# nguyenly.net
KiCad netlist of a schematic drawn in Altium Designer
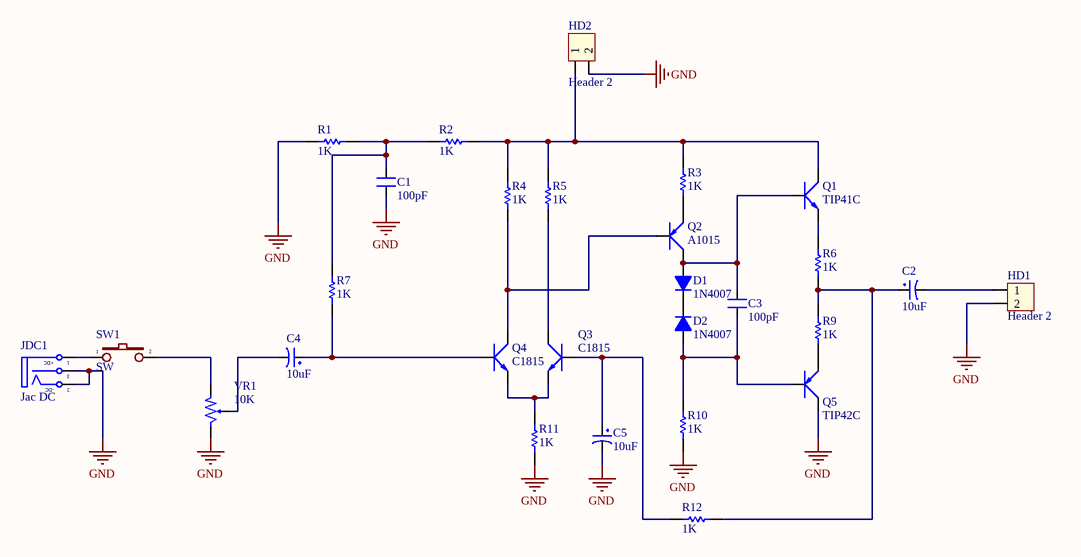
[diagram p0: nguyenly.SchDoc]

(export (version "E")
  (design (tool "Eeschema 10.0.6"))
  (components
    (comp (ref "C1")
      (value "100pF")
      (footprint "CN1")
      (description "Cap np  1pF - 472pF")
      (libsource (lib "Thuvien3D") (part "CN1"))
    )
    (comp (ref "C2")
      (value "10uF")
      (footprint "CP1/2")
      (description "Cap P  0,1uF < 22uF , 16 - 50V")
      (libsource (lib "") (part "CP1_1"))
    )
    (comp (ref "C3")
      (value "100pF")
      (footprint "CN1")
      (description "Cap np  1pF - 472pF")
      (libsource (lib "Thuvien3D") (part "CN1"))
    )
    (comp (ref "C4")
      (value "10uF")
      (footprint "CP1/2")
      (description "Cap P  0,1uF < 22uF , 16 - 50V")
      (libsource (lib "") (part "CP1_1"))
    )
    (comp (ref "C5")
      (value "10uF")
      (footprint "CP1/2")
      (description "Cap P  0,1uF < 22uF , 16 - 50V")
      (libsource (lib "Thuvien3D") (part "CP1"))
    )
    (comp (ref "D1")
      (value "1N4007")
      (footprint "D1A")
      (description "Diode 1A")
      (libsource (lib "Thuvien3D") (part "D1A"))
    )
    (comp (ref "D2")
      (value "1N4007")
      (footprint "D1A")
      (description "Diode 1A")
      (libsource (lib "Thuvien3D") (part "D1A"))
    )
    (comp (ref "HD1")
      (value "Header 2")
      (footprint "HED2")
      (description "Header 2 (Green)")
      (libsource (lib "Thuvien3D") (part "Hed2"))
    )
    (comp (ref "HD2")
      (value "Header 2")
      (footprint "HED2")
      (description "Header 2 (Green)")
      (libsource (lib "") (part "Hed2_1"))
    )
    (comp (ref "JDC1")
      (value "Jac DC")
      (footprint "DC-IN")
      (description "Jac DC input")
      (libsource (lib "Thuvien3D") (part "DCIN"))
    )
    (comp (ref "Q1")
      (value "TIP41C")
      (footprint "QTO-220")
      (description "NPN 2W, BCE")
      (libsource (lib "Thuvien3D") (part "TIP41C"))
    )
    (comp (ref "Q2")
      (value "A1015")
      (footprint "QTO-92")
      (description "PNP 600mW, ECB")
      (libsource (lib "Thuvien3D") (part "A1015"))
    )
    (comp (ref "Q3")
      (value "C1815")
      (footprint "QTO-92")
      (description "NPN 600mW, ECB")
      (libsource (lib "Thuvien3D") (part "C1815"))
    )
    (comp (ref "Q4")
      (value "C1815")
      (footprint "QTO-92")
      (description "NPN 600mW, ECB")
      (libsource (lib "Thuvien3D") (part "C1815"))
    )
    (comp (ref "Q5")
      (value "TIP42C")
      (footprint "QTO-220")
      (description "PNP 2W, BCE")
      (libsource (lib "Thuvien3D") (part "TIP42C"))
    )
    (comp (ref "R1")
      (value "1K")
      (footprint "R1/4W")
      (description "Resistor")
      (fields
        (field (name "MANUFACTURER") "Generic Components")
        (field (name "Comment") "Res1")
        (field (name "PUBLISHER") "Altium Hobart Technology Centre")
      )
      (libsource (lib "Thuvien3D") (part "Res1_1"))
    )
    (comp (ref "R2")
      (value "1K")
      (footprint "R1/4W")
      (description "Resistor")
      (fields
        (field (name "MANUFACTURER") "Generic Components")
        (field (name "Comment") "Res1")
        (field (name "PUBLISHER") "Altium Hobart Technology Centre")
      )
      (libsource (lib "Thuvien3D") (part "Res1_1"))
    )
    (comp (ref "R3")
      (value "1K")
      (footprint "R1/4W")
      (description "Resistor")
      (fields
        (field (name "MANUFACTURER") "Generic Components")
        (field (name "Comment") "Res1")
        (field (name "PUBLISHER") "Altium Hobart Technology Centre")
      )
      (libsource (lib "Thuvien3D") (part "Res1_1"))
    )
    (comp (ref "R4")
      (value "1K")
      (footprint "R1/4W")
      (description "Resistor")
      (fields
        (field (name "MANUFACTURER") "Generic Components")
        (field (name "Comment") "Res1")
        (field (name "PUBLISHER") "Altium Hobart Technology Centre")
      )
      (libsource (lib "Thuvien3D") (part "Res1_1"))
    )
    (comp (ref "R5")
      (value "1K")
      (footprint "R1/4W")
      (description "Resistor")
      (fields
        (field (name "MANUFACTURER") "Generic Components")
        (field (name "Comment") "Res1")
        (field (name "PUBLISHER") "Altium Hobart Technology Centre")
      )
      (libsource (lib "Thuvien3D") (part "Res1_1"))
    )
    (comp (ref "R6")
      (value "1K")
      (footprint "R1/4W")
      (description "Resistor")
      (fields
        (field (name "MANUFACTURER") "Generic Components")
        (field (name "Comment") "Res1")
        (field (name "PUBLISHER") "Altium Hobart Technology Centre")
      )
      (libsource (lib "Thuvien3D") (part "Res1_1"))
    )
    (comp (ref "R7")
      (value "1K")
      (footprint "R1/4W")
      (description "Resistor")
      (fields
        (field (name "MANUFACTURER") "Generic Components")
        (field (name "Comment") "Res1")
        (field (name "PUBLISHER") "Altium Hobart Technology Centre")
      )
      (libsource (lib "Thuvien3D") (part "Res1_1"))
    )
    (comp (ref "R9")
      (value "1K")
      (footprint "R1/4W")
      (description "Resistor")
      (fields
        (field (name "MANUFACTURER") "Generic Components")
        (field (name "Comment") "Res1")
        (field (name "PUBLISHER") "Altium Hobart Technology Centre")
      )
      (libsource (lib "Thuvien3D") (part "Res1_1"))
    )
    (comp (ref "R10")
      (value "1K")
      (footprint "R1/4W")
      (description "Resistor")
      (fields
        (field (name "MANUFACTURER") "Generic Components")
        (field (name "Comment") "Res1")
        (field (name "PUBLISHER") "Altium Hobart Technology Centre")
      )
      (libsource (lib "Thuvien3D") (part "Res1_1"))
    )
    (comp (ref "R11")
      (value "1K")
      (footprint "R1/4W")
      (description "Resistor")
      (fields
        (field (name "MANUFACTURER") "Generic Components")
        (field (name "Comment") "Res1")
        (field (name "PUBLISHER") "Altium Hobart Technology Centre")
      )
      (libsource (lib "Thuvien3D") (part "Res1_1"))
    )
    (comp (ref "R12")
      (value "1K")
      (footprint "R1/4W")
      (description "Resistor")
      (fields
        (field (name "MANUFACTURER") "Generic Components")
        (field (name "Comment") "Res1")
        (field (name "PUBLISHER") "Altium Hobart Technology Centre")
      )
      (libsource (lib "Thuvien3D") (part "Res1_1"))
    )
    (comp (ref "SW1")
      (value "SW")
      (footprint "SW2")
      (description "Switch button 2 pin")
      (libsource (lib "Thuvien3D") (part "SW2"))
    )
    (comp (ref "VR1")
      (value "10K")
      (footprint "VR")
      (description "Var Resistor")
      (libsource (lib "Thuvien3D") (part "VR1"))
    )
  )
  (nets
    (net (code "1") (name "GND") (class "Default")
      (node (ref "C1") (pin "1") (pinfunction "1_1") (pintype "passive"))
      (node (ref "C5") (pin "2") (pinfunction "2_2") (pintype "passive"))
      (node (ref "HD1") (pin "2") (pinfunction "2_2") (pintype "passive"))
      (node (ref "HD2") (pin "2") (pinfunction "2_2") (pintype "passive"))
      (node (ref "JDC1") (pin "2") (pinfunction "TN_2") (pintype "passive"))
      (node (ref "JDC1") (pin "3") (pinfunction "S_3") (pintype "power_in"))
      (node (ref "Q5") (pin "2") (pinfunction "C_2") (pintype "passive"))
      (node (ref "R1") (pin "2") (pinfunction "2_2") (pintype "passive"))
      (node (ref "R10") (pin "2") (pinfunction "2_2") (pintype "passive"))
      (node (ref "R11") (pin "2") (pinfunction "2_2") (pintype "passive"))
      (node (ref "VR1") (pin "3") (pinfunction "3_3") (pintype "passive"))
    )
    (net (code "2") (name "Net-(C1-Pad2)") (class "Default")
      (node (ref "C1") (pin "2") (pinfunction "2_2") (pintype "passive"))
      (node (ref "R1") (pin "1") (pinfunction "1_1") (pintype "passive"))
      (node (ref "R2") (pin "2") (pinfunction "2_2") (pintype "passive"))
      (node (ref "R7") (pin "1") (pinfunction "1_1") (pintype "passive"))
    )
    (net (code "3") (name "Net-(C2-Pad1)") (class "Default")
      (node (ref "C2") (pin "1") (pinfunction "1_1") (pintype "passive"))
      (node (ref "R12") (pin "2") (pinfunction "2_2") (pintype "passive"))
      (node (ref "R6") (pin "2") (pinfunction "2_2") (pintype "passive"))
      (node (ref "R9") (pin "1") (pinfunction "1_1") (pintype "passive"))
    )
    (net (code "4") (name "Net-(C2-Pad2)") (class "Default")
      (node (ref "C2") (pin "2") (pinfunction "2_2") (pintype "passive"))
      (node (ref "HD1") (pin "1") (pinfunction "1_1") (pintype "passive"))
    )
    (net (code "5") (name "Net-(C4-Pad2)") (class "Default")
      (node (ref "C4") (pin "2") (pinfunction "2_2") (pintype "passive"))
      (node (ref "VR1") (pin "2") (pinfunction "2_2") (pintype "passive"))
    )
    (net (code "6") (name "Net-(D1-A)") (class "Default")
      (node (ref "C3") (pin "2") (pinfunction "2_2") (pintype "passive"))
      (node (ref "D1") (pin "1") (pinfunction "A_1") (pintype "passive"))
      (node (ref "Q1") (pin "1") (pinfunction "B_1") (pintype "passive"))
      (node (ref "Q2") (pin "2") (pinfunction "C_2") (pintype "passive"))
    )
    (net (code "7") (name "Net-(D1-K)") (class "Default")
      (node (ref "D1") (pin "2") (pinfunction "K_2") (pintype "passive"))
      (node (ref "D2") (pin "2") (pinfunction "K_2") (pintype "passive"))
    )
    (net (code "8") (name "Net-(D2-A)") (class "Default")
      (node (ref "C3") (pin "1") (pinfunction "1_1") (pintype "passive"))
      (node (ref "D2") (pin "1") (pinfunction "A_1") (pintype "passive"))
      (node (ref "Q5") (pin "1") (pinfunction "B_1") (pintype "passive"))
      (node (ref "R10") (pin "1") (pinfunction "1_1") (pintype "passive"))
    )
    (net (code "9") (name "Net-(JDC1-T)") (class "Default")
      (node (ref "JDC1") (pin "1") (pinfunction "T_1") (pintype "passive"))
      (node (ref "SW1") (pin "1") (pinfunction "1_1") (pintype "passive"))
    )
    (net (code "10") (name "Net-(Q1-C)") (class "Default")
      (node (ref "HD2") (pin "1") (pinfunction "1_1") (pintype "passive"))
      (node (ref "Q1") (pin "2") (pinfunction "C_2") (pintype "passive"))
      (node (ref "R2") (pin "1") (pinfunction "1_1") (pintype "passive"))
      (node (ref "R3") (pin "1") (pinfunction "1_1") (pintype "passive"))
      (node (ref "R4") (pin "1") (pinfunction "1_1") (pintype "passive"))
      (node (ref "R5") (pin "1") (pinfunction "1_1") (pintype "passive"))
    )
    (net (code "11") (name "Net-(Q1-E)") (class "Default")
      (node (ref "Q1") (pin "3") (pinfunction "E_3") (pintype "passive"))
      (node (ref "R6") (pin "1") (pinfunction "1_1") (pintype "passive"))
    )
    (net (code "12") (name "Net-(Q2-B)") (class "Default")
      (node (ref "Q2") (pin "3") (pinfunction "B_3") (pintype "passive"))
      (node (ref "Q4") (pin "2") (pinfunction "C_2") (pintype "passive"))
      (node (ref "R4") (pin "2") (pinfunction "2_2") (pintype "passive"))
    )
    (net (code "13") (name "Net-(Q2-E)") (class "Default")
      (node (ref "Q2") (pin "1") (pinfunction "E_1") (pintype "passive"))
      (node (ref "R3") (pin "2") (pinfunction "2_2") (pintype "passive"))
    )
    (net (code "14") (name "Net-(Q3-B)") (class "Default")
      (node (ref "C5") (pin "1") (pinfunction "1_1") (pintype "passive"))
      (node (ref "Q3") (pin "3") (pinfunction "B_3") (pintype "passive"))
      (node (ref "R12") (pin "1") (pinfunction "1_1") (pintype "passive"))
    )
    (net (code "15") (name "Net-(Q3-C)") (class "Default")
      (node (ref "Q3") (pin "2") (pinfunction "C_2") (pintype "passive"))
      (node (ref "R5") (pin "2") (pinfunction "2_2") (pintype "passive"))
    )
    (net (code "16") (name "Net-(Q3-E)") (class "Default")
      (node (ref "Q3") (pin "1") (pinfunction "E_1") (pintype "passive"))
      (node (ref "Q4") (pin "1") (pinfunction "E_1") (pintype "passive"))
      (node (ref "R11") (pin "1") (pinfunction "1_1") (pintype "passive"))
    )
    (net (code "17") (name "Net-(Q4-B)") (class "Default")
      (node (ref "C4") (pin "1") (pinfunction "1_1") (pintype "passive"))
      (node (ref "Q4") (pin "3") (pinfunction "B_3") (pintype "passive"))
      (node (ref "R7") (pin "2") (pinfunction "2_2") (pintype "passive"))
    )
    (net (code "18") (name "Net-(Q5-E)") (class "Default")
      (node (ref "Q5") (pin "3") (pinfunction "E_3") (pintype "passive"))
      (node (ref "R9") (pin "2") (pinfunction "2_2") (pintype "passive"))
    )
    (net (code "19") (name "Net-(SW1-Pad2)") (class "Default")
      (node (ref "SW1") (pin "2") (pinfunction "2_2") (pintype "passive"))
      (node (ref "VR1") (pin "1") (pinfunction "1_1") (pintype "passive"))
    )
  )
)
